# CANSAT.net
KiCad netlist of a schematic drawn in EAGLE
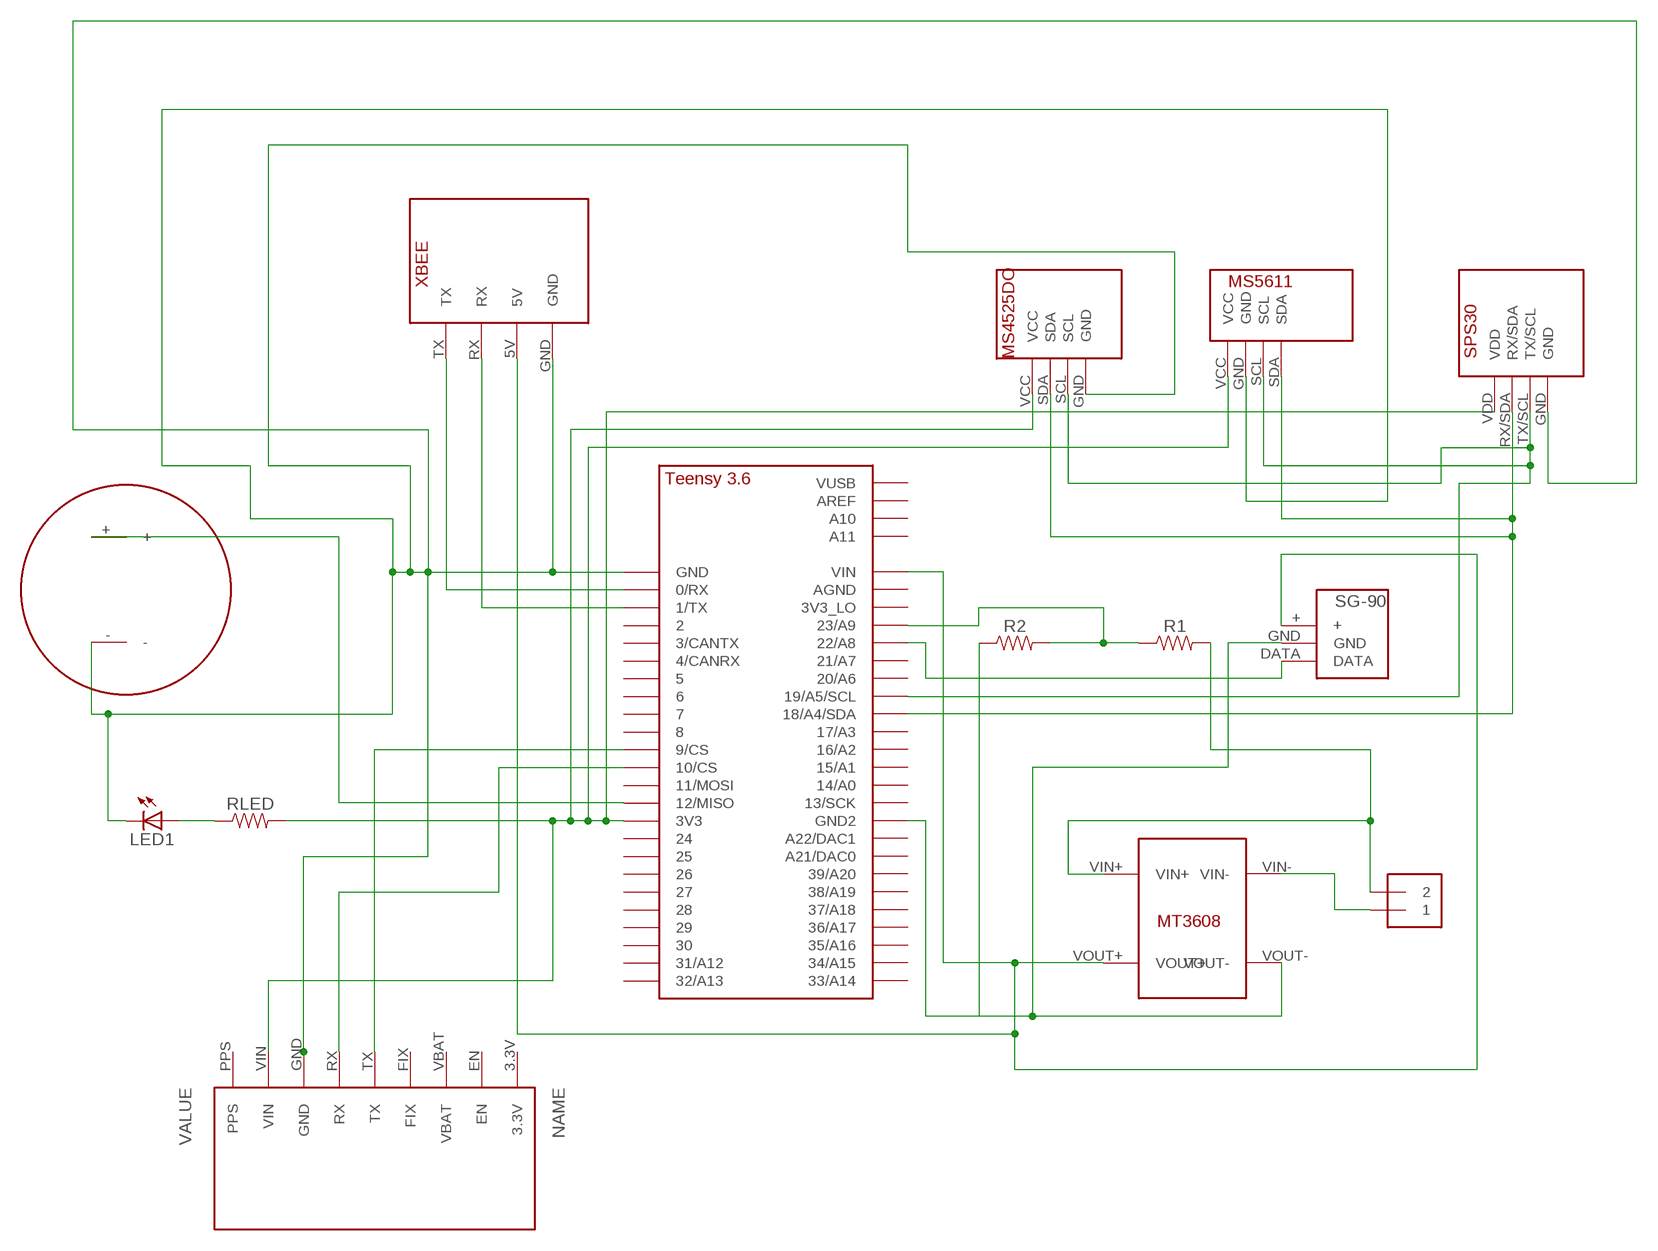
[diagram p0: schematic, sheet 1]

(export (version "E")
  (design (tool "Eeschema 10.0.6"))
  (components
    (comp (ref "GPS1")
      (value "ADAFRUITGPSBREAKOUT")
      (footprint "eagle-import:ADAFRUITGPS")
      (libsource (lib "eagle-import") (part "ADAFRUITGPSBREAKOUT"))
    )
    (comp (ref "J1")
      (value "1X2-3.5MM")
      (footprint "eagle-import:1X2-3.5MM")
      (libsource (lib "eagle-import") (part "1X2-3.5MM"))
    )
    (comp (ref "LED1")
      (value "LED5MM")
      (footprint "eagle-import:LED5MM")
      (libsource (lib "eagle-import") (part "LED5MM"))
    )
    (comp (ref "R1")
      (value "1.2K")
      (footprint "eagle-import:AXIAL-0.3")
      (libsource (lib "eagle-import") (part "RESISTORAXIAL-0.3"))
    )
    (comp (ref "R2")
      (value "2.5K")
      (footprint "eagle-import:AXIAL-0.3")
      (libsource (lib "eagle-import") (part "RESISTORAXIAL-0.3"))
    )
    (comp (ref "RLED")
      (value "220")
      (footprint "eagle-import:AXIAL-0.3")
      (libsource (lib "eagle-import") (part "RESISTORAXIAL-0.3"))
    )
    (comp (ref "U$1")
      (value "MT3608")
      (footprint "eagle-import:MT3608")
      (libsource (lib "eagle-import") (part "MT3608"))
    )
    (comp (ref "U$2")
      (value "TEENSY_3.5/3.6_BASIC")
      (footprint "eagle-import:TEENSY_3.5_3.6_BASIC")
      (libsource (lib "eagle-import") (part "TEENSY_3.5/3.6_BASIC"))
    )
    (comp (ref "U$3")
      (value "XBEE-S2CPRO")
      (footprint "eagle-import:XBEE-S2CPRO")
      (libsource (lib "eagle-import") (part "XBEE-S2CPRO"))
    )
    (comp (ref "U$4")
      (value "MS4525DO")
      (footprint "eagle-import:MS4525DO")
      (libsource (lib "eagle-import") (part "MS4525DO"))
    )
    (comp (ref "U$5")
      (value "MS5611")
      (footprint "eagle-import:MS5611")
      (libsource (lib "eagle-import") (part "MS5611"))
    )
    (comp (ref "U$6")
      (value "SPS30")
      (footprint "eagle-import:SPS30")
      (libsource (lib "eagle-import") (part "SPS30"))
    )
    (comp (ref "U$7")
      (value "AL-3035")
      (footprint "eagle-import:BUZZER")
      (libsource (lib "eagle-import") (part "AL-3035"))
    )
    (comp (ref "U$8")
      (value "SG-90")
      (footprint "eagle-import:SG-90")
      (libsource (lib "eagle-import") (part "SG-90"))
    )
  )
  (nets
    (net (code "1") (name "Net-(GPS1-PadRX)") (class "Default")
      (node (ref "GPS1") (pin "RX") (pinfunction "RX_RX") (pintype "bidirectional"))
      (node (ref "U$2") (pin "10/CS") (pinfunction "10/CS_10/CS") (pintype "bidirectional"))
    )
    (net (code "2") (name "Net-(GPS1-PadTX)") (class "Default")
      (node (ref "GPS1") (pin "TX") (pinfunction "TX_TX") (pintype "bidirectional"))
      (node (ref "U$2") (pin "9/CS") (pinfunction "9/CS_9/CS") (pintype "bidirectional"))
    )
    (net (code "3") (name "Net-(J1-Pad1)") (class "Default")
      (node (ref "J1") (pin "1") (pinfunction "1_1") (pintype "passive"))
      (node (ref "U$1") (pin "VIN-") (pinfunction "VIN-_VIN-") (pintype "bidirectional"))
    )
    (net (code "4") (name "Net-(LED1-C)") (class "Default")
      (node (ref "GPS1") (pin "GND") (pinfunction "GND_GND") (pintype "bidirectional"))
      (node (ref "LED1") (pin "K") (pinfunction "C_K") (pintype "passive"))
      (node (ref "U$2") (pin "GND") (pinfunction "GND_GND") (pintype "bidirectional"))
      (node (ref "U$3") (pin "GND") (pinfunction "GND_GND") (pintype "bidirectional"))
      (node (ref "U$4") (pin "GND") (pinfunction "GND_GND") (pintype "bidirectional"))
      (node (ref "U$5") (pin "GND") (pinfunction "GND_GND") (pintype "bidirectional"))
      (node (ref "U$6") (pin "GND") (pinfunction "GND_GND") (pintype "bidirectional"))
      (node (ref "U$7") (pin "-") (pinfunction "-_-") (pintype "bidirectional"))
    )
    (net (code "5") (name "Net-(R1-1)") (class "Default")
      (node (ref "R1") (pin "P$1") (pinfunction "1_P$1") (pintype "passive"))
      (node (ref "R2") (pin "P$2") (pinfunction "2_P$2") (pintype "passive"))
      (node (ref "U$2") (pin "23/A9") (pinfunction "23/A9_23/A9") (pintype "bidirectional"))
    )
    (net (code "6") (name "Net-(R1-2)") (class "Default")
      (node (ref "J1") (pin "2") (pinfunction "2_2") (pintype "passive"))
      (node (ref "R1") (pin "P$2") (pinfunction "2_P$2") (pintype "passive"))
      (node (ref "U$1") (pin "VIN+") (pinfunction "VIN+_VIN+") (pintype "bidirectional"))
    )
    (net (code "7") (name "Net-(R2-1)") (class "Default")
      (node (ref "R2") (pin "P$1") (pinfunction "1_P$1") (pintype "passive"))
      (node (ref "U$1") (pin "VOUT-") (pinfunction "VOUT-_VOUT-") (pintype "bidirectional"))
      (node (ref "U$2") (pin "GND2") (pinfunction "GND2_GND2") (pintype "bidirectional"))
      (node (ref "U$8") (pin "GND") (pinfunction "GND_GND") (pintype "bidirectional"))
    )
    (net (code "8") (name "Net-(RLED-1)") (class "Default")
      (node (ref "LED1") (pin "A") (pinfunction "A_A") (pintype "passive"))
      (node (ref "RLED") (pin "P$1") (pinfunction "1_P$1") (pintype "passive"))
    )
    (net (code "9") (name "Net-(RLED-2)") (class "Default")
      (node (ref "GPS1") (pin "VIN") (pinfunction "VIN_VIN") (pintype "bidirectional"))
      (node (ref "RLED") (pin "P$2") (pinfunction "2_P$2") (pintype "passive"))
      (node (ref "U$2") (pin "3V3") (pinfunction "3V3_3V3") (pintype "bidirectional"))
      (node (ref "U$4") (pin "VCC") (pinfunction "VCC_VCC") (pintype "bidirectional"))
      (node (ref "U$5") (pin "VCC") (pinfunction "VCC_VCC") (pintype "bidirectional"))
      (node (ref "U$6") (pin "VDD") (pinfunction "VDD_VDD") (pintype "bidirectional"))
    )
    (net (code "10") (name "Net-(U$1-PadVOUT+)") (class "Default")
      (node (ref "U$1") (pin "VOUT+") (pinfunction "VOUT+_VOUT+") (pintype "bidirectional"))
      (node (ref "U$2") (pin "VIN") (pinfunction "VIN_VIN") (pintype "bidirectional"))
      (node (ref "U$3") (pin "5V") (pinfunction "5V_5V") (pintype "bidirectional"))
      (node (ref "U$8") (pin "+") (pinfunction "+_+") (pintype "bidirectional"))
    )
    (net (code "11") (name "Net-(U$2-Pad0{slash}RX)") (class "Default")
      (node (ref "U$2") (pin "0/RX") (pinfunction "0/RX_0/RX") (pintype "bidirectional"))
      (node (ref "U$3") (pin "TX") (pinfunction "TX_TX") (pintype "bidirectional"))
    )
    (net (code "12") (name "Net-(U$2-Pad1{slash}TX)") (class "Default")
      (node (ref "U$2") (pin "1/TX") (pinfunction "1/TX_1/TX") (pintype "bidirectional"))
      (node (ref "U$3") (pin "RX") (pinfunction "RX_RX") (pintype "bidirectional"))
    )
    (net (code "13") (name "Net-(U$2-Pad12{slash}MISO)") (class "Default")
      (node (ref "U$2") (pin "12/MISO") (pinfunction "12/MISO_12/MISO") (pintype "bidirectional"))
      (node (ref "U$7") (pin "+") (pinfunction "+_+") (pintype "bidirectional"))
    )
    (net (code "14") (name "Net-(U$2-Pad18{slash}A4{slash}SDA)") (class "Default")
      (node (ref "U$2") (pin "18/A4/SDA") (pinfunction "18/A4/SDA_18/A4/SDA") (pintype "bidirectional"))
      (node (ref "U$4") (pin "SDA") (pinfunction "SDA_SDA") (pintype "bidirectional"))
      (node (ref "U$5") (pin "SDA") (pinfunction "SDA_SDA") (pintype "bidirectional"))
      (node (ref "U$6") (pin "RX/SDA") (pinfunction "RX/SDA_RX/SDA") (pintype "bidirectional"))
    )
    (net (code "15") (name "Net-(U$2-Pad19{slash}A5{slash}SCL)") (class "Default")
      (node (ref "U$2") (pin "19/A5/SCL") (pinfunction "19/A5/SCL_19/A5/SCL") (pintype "bidirectional"))
      (node (ref "U$4") (pin "SCL") (pinfunction "SCL_SCL") (pintype "bidirectional"))
      (node (ref "U$5") (pin "SCL") (pinfunction "SCL_SCL") (pintype "bidirectional"))
      (node (ref "U$6") (pin "TX/SCL") (pinfunction "TX/SCL_TX/SCL") (pintype "bidirectional"))
    )
    (net (code "16") (name "Net-(U$2-Pad22{slash}A8)") (class "Default")
      (node (ref "U$2") (pin "22/A8") (pinfunction "22/A8_22/A8") (pintype "bidirectional"))
      (node (ref "U$8") (pin "DATA") (pinfunction "DATA_DATA") (pintype "bidirectional"))
    )
    (net (code "17") (name "unconnected-(GPS1-Pad3.3V)") (class "Default")
      (node (ref "GPS1") (pin "3.3V") (pinfunction "3.3V_3.3V") (pintype "bidirectional"))
    )
    (net (code "18") (name "unconnected-(GPS1-PadEN)") (class "Default")
      (node (ref "GPS1") (pin "EN") (pinfunction "EN_EN") (pintype "bidirectional"))
    )
    (net (code "19") (name "unconnected-(GPS1-PadFIX)") (class "Default")
      (node (ref "GPS1") (pin "FIX") (pinfunction "FIX_FIX") (pintype "bidirectional"))
    )
    (net (code "20") (name "unconnected-(GPS1-PadPPS)") (class "Default")
      (node (ref "GPS1") (pin "PPS") (pinfunction "PPS_PPS") (pintype "bidirectional"))
    )
    (net (code "21") (name "unconnected-(GPS1-PadVBAT)") (class "Default")
      (node (ref "GPS1") (pin "VBAT") (pinfunction "VBAT_VBAT") (pintype "bidirectional"))
    )
    (net (code "22") (name "unconnected-(U$2-A21{slash}DAC0-Pad21{slash}DAC0)") (class "Default")
      (node (ref "U$2") (pin "21/DAC0") (pinfunction "A21/DAC0_21/DAC0") (pintype "bidirectional"))
    )
    (net (code "23") (name "unconnected-(U$2-Pad2)") (class "Default")
      (node (ref "U$2") (pin "2") (pinfunction "2_2") (pintype "bidirectional"))
    )
    (net (code "24") (name "unconnected-(U$2-Pad3V3_LO)") (class "Default")
      (node (ref "U$2") (pin "3V3_LO") (pinfunction "3V3_LO_3V3_LO") (pintype "bidirectional"))
    )
    (net (code "25") (name "unconnected-(U$2-Pad3{slash}CANTX)") (class "Default")
      (node (ref "U$2") (pin "3/CANTX") (pinfunction "3/CANTX_3/CANTX") (pintype "bidirectional"))
    )
    (net (code "26") (name "unconnected-(U$2-Pad4{slash}CANRX)") (class "Default")
      (node (ref "U$2") (pin "4/CANRX") (pinfunction "4/CANRX_4/CANRX") (pintype "bidirectional"))
    )
    (net (code "27") (name "unconnected-(U$2-Pad5)") (class "Default")
      (node (ref "U$2") (pin "5") (pinfunction "5_5") (pintype "bidirectional"))
    )
    (net (code "28") (name "unconnected-(U$2-Pad6)") (class "Default")
      (node (ref "U$2") (pin "6") (pinfunction "6_6") (pintype "bidirectional"))
    )
    (net (code "29") (name "unconnected-(U$2-Pad7)") (class "Default")
      (node (ref "U$2") (pin "7") (pinfunction "7_7") (pintype "bidirectional"))
    )
    (net (code "30") (name "unconnected-(U$2-Pad8)") (class "Default")
      (node (ref "U$2") (pin "8") (pinfunction "8_8") (pintype "bidirectional"))
    )
    (net (code "31") (name "unconnected-(U$2-Pad11{slash}MOSI)") (class "Default")
      (node (ref "U$2") (pin "11/MOSI") (pinfunction "11/MOSI_11/MOSI") (pintype "bidirectional"))
    )
    (net (code "32") (name "unconnected-(U$2-Pad13{slash}SCK)") (class "Default")
      (node (ref "U$2") (pin "13/SCK") (pinfunction "13/SCK_13/SCK") (pintype "bidirectional"))
    )
    (net (code "33") (name "unconnected-(U$2-Pad14{slash}A0)") (class "Default")
      (node (ref "U$2") (pin "14/A0") (pinfunction "14/A0_14/A0") (pintype "bidirectional"))
    )
    (net (code "34") (name "unconnected-(U$2-Pad15{slash}A1)") (class "Default")
      (node (ref "U$2") (pin "15/A1") (pinfunction "15/A1_15/A1") (pintype "bidirectional"))
    )
    (net (code "35") (name "unconnected-(U$2-Pad16{slash}A2)") (class "Default")
      (node (ref "U$2") (pin "16/A2") (pinfunction "16/A2_16/A2") (pintype "bidirectional"))
    )
    (net (code "36") (name "unconnected-(U$2-Pad17{slash}A3)") (class "Default")
      (node (ref "U$2") (pin "17/A3") (pinfunction "17/A3_17/A3") (pintype "bidirectional"))
    )
    (net (code "37") (name "unconnected-(U$2-Pad20{slash}A6)") (class "Default")
      (node (ref "U$2") (pin "20/A6") (pinfunction "20/A6_20/A6") (pintype "bidirectional"))
    )
    (net (code "38") (name "unconnected-(U$2-Pad21{slash}A7)") (class "Default")
      (node (ref "U$2") (pin "21/A7") (pinfunction "21/A7_21/A7") (pintype "bidirectional"))
    )
    (net (code "39") (name "unconnected-(U$2-Pad24)") (class "Default")
      (node (ref "U$2") (pin "24") (pinfunction "24_24") (pintype "bidirectional"))
    )
    (net (code "40") (name "unconnected-(U$2-Pad25)") (class "Default")
      (node (ref "U$2") (pin "25") (pinfunction "25_25") (pintype "bidirectional"))
    )
    (net (code "41") (name "unconnected-(U$2-Pad26)") (class "Default")
      (node (ref "U$2") (pin "26") (pinfunction "26_26") (pintype "bidirectional"))
    )
    (net (code "42") (name "unconnected-(U$2-Pad27)") (class "Default")
      (node (ref "U$2") (pin "27") (pinfunction "27_27") (pintype "bidirectional"))
    )
    (net (code "43") (name "unconnected-(U$2-Pad28)") (class "Default")
      (node (ref "U$2") (pin "28") (pinfunction "28_28") (pintype "bidirectional"))
    )
    (net (code "44") (name "unconnected-(U$2-Pad29)") (class "Default")
      (node (ref "U$2") (pin "29") (pinfunction "29_29") (pintype "bidirectional"))
    )
    (net (code "45") (name "unconnected-(U$2-Pad30)") (class "Default")
      (node (ref "U$2") (pin "30") (pinfunction "30_30") (pintype "bidirectional"))
    )
    (net (code "46") (name "unconnected-(U$2-Pad31{slash}A12)") (class "Default")
      (node (ref "U$2") (pin "31/A12") (pinfunction "31/A12_31/A12") (pintype "bidirectional"))
    )
    (net (code "47") (name "unconnected-(U$2-Pad32{slash}A13)") (class "Default")
      (node (ref "U$2") (pin "32/A13") (pinfunction "32/A13_32/A13") (pintype "bidirectional"))
    )
    (net (code "48") (name "unconnected-(U$2-Pad33{slash}A14)") (class "Default")
      (node (ref "U$2") (pin "33/A14") (pinfunction "33/A14_33/A14") (pintype "bidirectional"))
    )
    (net (code "49") (name "unconnected-(U$2-Pad34{slash}A15)") (class "Default")
      (node (ref "U$2") (pin "34/A15") (pinfunction "34/A15_34/A15") (pintype "bidirectional"))
    )
    (net (code "50") (name "unconnected-(U$2-Pad35{slash}A16)") (class "Default")
      (node (ref "U$2") (pin "35/A16") (pinfunction "35/A16_35/A16") (pintype "bidirectional"))
    )
    (net (code "51") (name "unconnected-(U$2-Pad36{slash}A17)") (class "Default")
      (node (ref "U$2") (pin "36/A17") (pinfunction "36/A17_36/A17") (pintype "bidirectional"))
    )
    (net (code "52") (name "unconnected-(U$2-Pad37{slash}A18)") (class "Default")
      (node (ref "U$2") (pin "37/A18") (pinfunction "37/A18_37/A18") (pintype "bidirectional"))
    )
    (net (code "53") (name "unconnected-(U$2-Pad38{slash}A19)") (class "Default")
      (node (ref "U$2") (pin "38/A19") (pinfunction "38/A19_38/A19") (pintype "bidirectional"))
    )
    (net (code "54") (name "unconnected-(U$2-Pad39{slash}A20)") (class "Default")
      (node (ref "U$2") (pin "39/A20") (pinfunction "39/A20_39/A20") (pintype "bidirectional"))
    )
    (net (code "55") (name "unconnected-(U$2-PadA10)") (class "Default")
      (node (ref "U$2") (pin "A10") (pinfunction "A10_A10") (pintype "bidirectional"))
    )
    (net (code "56") (name "unconnected-(U$2-PadA11)") (class "Default")
      (node (ref "U$2") (pin "A11") (pinfunction "A11_A11") (pintype "bidirectional"))
    )
    (net (code "57") (name "unconnected-(U$2-PadA22{slash}DAC1)") (class "Default")
      (node (ref "U$2") (pin "A22/DAC1") (pinfunction "A22/DAC1_A22/DAC1") (pintype "bidirectional"))
    )
    (net (code "58") (name "unconnected-(U$2-PadAGND)") (class "Default")
      (node (ref "U$2") (pin "AGND") (pinfunction "AGND_AGND") (pintype "bidirectional"))
    )
    (net (code "59") (name "unconnected-(U$2-PadAREF)") (class "Default")
      (node (ref "U$2") (pin "AREF") (pinfunction "AREF_AREF") (pintype "bidirectional"))
    )
    (net (code "60") (name "unconnected-(U$2-PadVUSB)") (class "Default")
      (node (ref "U$2") (pin "VUSB") (pinfunction "VUSB_VUSB") (pintype "bidirectional"))
    )
  )
)
